# Power_MPU.net
KiCad netlist of a schematic drawn in Altium Designer
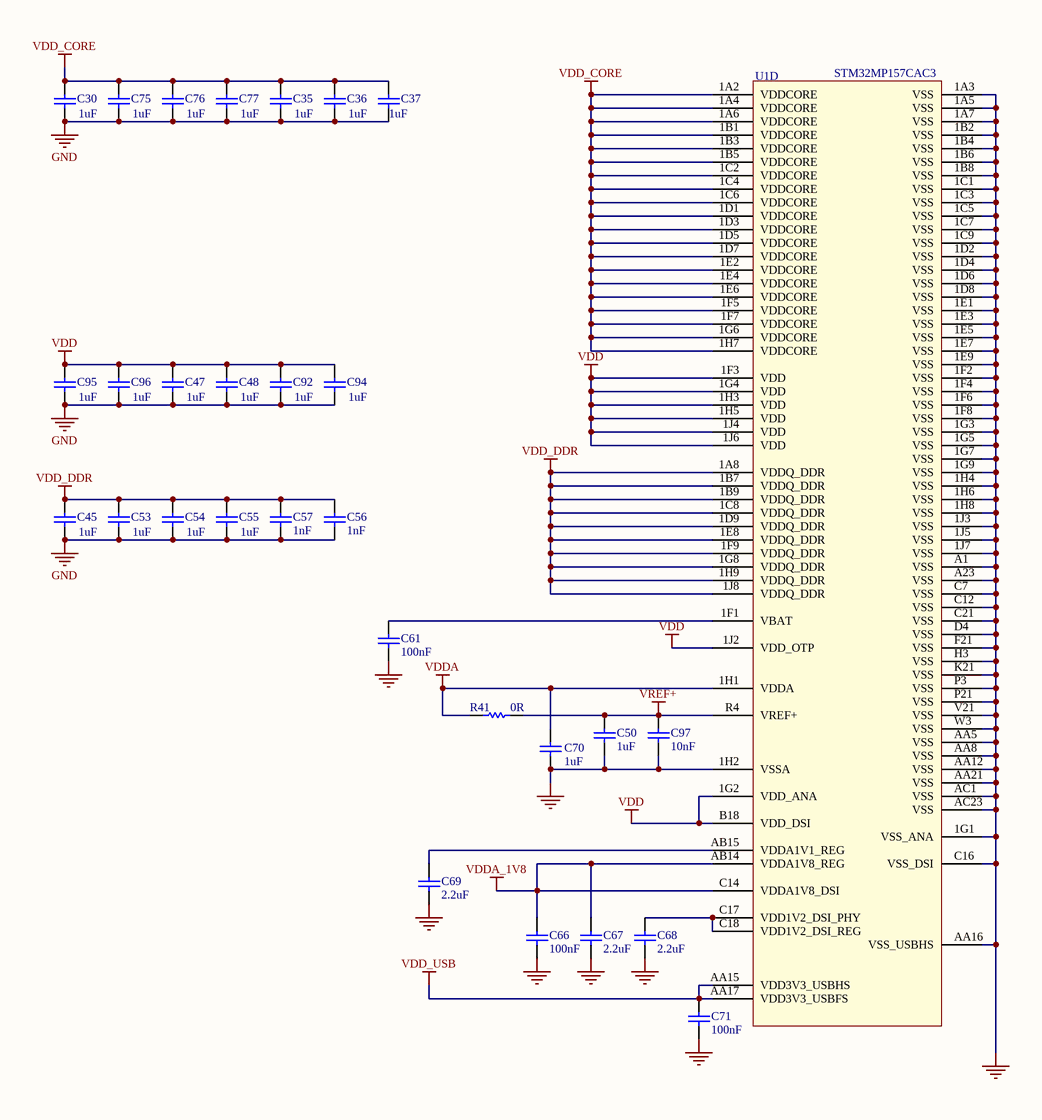
[diagram p0: Power_MPU.SchDoc]

(export (version "E")
  (design (tool "Eeschema 10.0.6"))
  (components
    (comp (ref "C30")
      (value "1uF")
      (footprint "C0402")
      (description "Capacitor,1uF,6V3,X5R,10%,0402")
      (fields
        (field (name "INTERNAL_PART_NUMBER") "MCD-00095")
        (field (name "MANUFACTURER_PART_NUMBER") "GRM155R60J105KE19")
        (field (name "PROVIDED_BY") "Subcon")
      )
      (libsource (lib "MCD_PARTS_database") (part "Capacitor"))
    )
    (comp (ref "C35")
      (value "1uF")
      (footprint "C0402")
      (description "Capacitor,1uF,6V3,X5R,10%,0402")
      (fields
        (field (name "INTERNAL_PART_NUMBER") "MCD-00095")
        (field (name "MANUFACTURER_PART_NUMBER") "GRM155R60J105KE19")
        (field (name "PROVIDED_BY") "Subcon")
      )
      (libsource (lib "MCD_PARTS_database") (part "Capacitor"))
    )
    (comp (ref "C36")
      (value "1uF")
      (footprint "C0402")
      (description "Capacitor,1uF,6V3,X5R,10%,0402")
      (fields
        (field (name "INTERNAL_PART_NUMBER") "MCD-00095")
        (field (name "MANUFACTURER_PART_NUMBER") "GRM155R60J105KE19")
        (field (name "PROVIDED_BY") "Subcon")
      )
      (libsource (lib "MCD_PARTS_database") (part "Capacitor"))
    )
    (comp (ref "C37")
      (value "1uF")
      (footprint "C0402")
      (description "Capacitor,1uF,6V3,X5R,10%,0402")
      (fields
        (field (name "INTERNAL_PART_NUMBER") "MCD-00095")
        (field (name "MANUFACTURER_PART_NUMBER") "GRM155R60J105KE19")
        (field (name "PROVIDED_BY") "Subcon")
      )
      (libsource (lib "MCD_PARTS_database") (part "Capacitor"))
    )
    (comp (ref "C45")
      (value "1uF")
      (footprint "C0402")
      (description "Capacitor,1uF,6V3,X5R,10%,0402")
      (fields
        (field (name "INTERNAL_PART_NUMBER") "MCD-00095")
        (field (name "MANUFACTURER_PART_NUMBER") "GRM155R60J105KE19")
        (field (name "PROVIDED_BY") "Subcon")
      )
      (libsource (lib "MCD_PARTS_database") (part "Capacitor"))
    )
    (comp (ref "C47")
      (value "1uF")
      (footprint "C0402")
      (description "Capacitor,1uF,6V3,X5R,10%,0402")
      (fields
        (field (name "INTERNAL_PART_NUMBER") "MCD-00095")
        (field (name "MANUFACTURER_PART_NUMBER") "GRM155R60J105KE19")
        (field (name "PROVIDED_BY") "Subcon")
      )
      (libsource (lib "MCD_PARTS_database") (part "Capacitor"))
    )
    (comp (ref "C48")
      (value "1uF")
      (footprint "C0402")
      (description "Capacitor,1uF,6V3,X5R,10%,0402")
      (fields
        (field (name "INTERNAL_PART_NUMBER") "MCD-00095")
        (field (name "MANUFACTURER_PART_NUMBER") "GRM155R60J105KE19")
        (field (name "PROVIDED_BY") "Subcon")
      )
      (libsource (lib "MCD_PARTS_database") (part "Capacitor"))
    )
    (comp (ref "C50")
      (value "1uF")
      (footprint "C0402")
      (description "Capacitor,1uF,6V3,X5R,10%,0402")
      (fields
        (field (name "INTERNAL_PART_NUMBER") "MCD-00095")
        (field (name "MANUFACTURER_PART_NUMBER") "GRM155R60J105KE19")
        (field (name "PROVIDED_BY") "Subcon")
      )
      (libsource (lib "MCD_PARTS_database") (part "Capacitor"))
    )
    (comp (ref "C53")
      (value "1uF")
      (footprint "C0402")
      (description "Capacitor,1uF,6V3,X5R,10%,0402")
      (fields
        (field (name "INTERNAL_PART_NUMBER") "MCD-00095")
        (field (name "MANUFACTURER_PART_NUMBER") "GRM155R60J105KE19")
        (field (name "PROVIDED_BY") "Subcon")
      )
      (libsource (lib "MCD_PARTS_database") (part "Capacitor"))
    )
    (comp (ref "C54")
      (value "1uF")
      (footprint "C0402")
      (description "Capacitor,1uF,6V3,X5R,10%,0402")
      (fields
        (field (name "INTERNAL_PART_NUMBER") "MCD-00095")
        (field (name "MANUFACTURER_PART_NUMBER") "GRM155R60J105KE19")
        (field (name "PROVIDED_BY") "Subcon")
      )
      (libsource (lib "MCD_PARTS_database") (part "Capacitor"))
    )
    (comp (ref "C55")
      (value "1uF")
      (footprint "C0402")
      (description "Capacitor,1uF,6V3,X5R,10%,0402")
      (fields
        (field (name "INTERNAL_PART_NUMBER") "MCD-00095")
        (field (name "MANUFACTURER_PART_NUMBER") "GRM155R60J105KE19")
        (field (name "PROVIDED_BY") "Subcon")
      )
      (libsource (lib "MCD_PARTS_database") (part "Capacitor"))
    )
    (comp (ref "C56")
      (value "1nF")
      (footprint "C0402")
      (description "Capacitor,1nF,16V,X7R,10%,0402")
      (fields
        (field (name "INTERNAL_PART_NUMBER") "MCD-00198")
        (field (name "MANUFACTURER_PART_NUMBER") "CC0402KRX7R7BB102")
        (field (name "PROVIDED_BY") "Subcon")
      )
      (libsource (lib "MCD_PARTS_database") (part "Capacitor"))
    )
    (comp (ref "C57")
      (value "1nF")
      (footprint "C0402")
      (description "Capacitor,1nF,16V,X7R,10%,0402")
      (fields
        (field (name "INTERNAL_PART_NUMBER") "MCD-00198")
        (field (name "MANUFACTURER_PART_NUMBER") "CC0402KRX7R7BB102")
        (field (name "PROVIDED_BY") "Subcon")
      )
      (libsource (lib "MCD_PARTS_database") (part "Capacitor"))
    )
    (comp (ref "C61")
      (value "100nF")
      (footprint "C0402")
      (description "Capacitor,100nF,16V,X7R,10%,0402")
      (fields
        (field (name "INTERNAL_PART_NUMBER") "MCD-00006")
        (field (name "MANUFACTURER_PART_NUMBER") "CC0402KRX7R7BB104")
        (field (name "PROVIDED_BY") "Subcon")
      )
      (libsource (lib "MCD_PARTS_database") (part "Capacitor"))
    )
    (comp (ref "C66")
      (value "100nF")
      (footprint "C0402")
      (description "Capacitor, MLCC, 100nF, 16V, X7R, 10%, 0402, T=0.5mm")
      (fields
        (field (name "INTERNAL_PART_NUMBER") "MCD-00006")
        (field (name "MANUFACTURER_PART_NUMBER") "CC0402KRX7R7BB104")
        (field (name "PROVIDED_BY") "SUBCO")
      )
      (libsource (lib "MCD_PARTS_database") (part "Capacitor"))
    )
    (comp (ref "C67")
      (value "2.2uF")
      (footprint "C0402")
      (description "Capacitor,MLCC,2.2uF,6V3,X5R,10%,0402,T=0.5")
      (fields
        (field (name "INTERNAL_PART_NUMBER") "MCD-01823")
        (field (name "MANUFACTURER_PART_NUMBER") "GRM155R60J225KE95D")
        (field (name "PROVIDED_BY") "SUBCO")
      )
      (libsource (lib "MCD_PARTS_database") (part "Capacitor"))
    )
    (comp (ref "C68")
      (value "2.2uF")
      (footprint "C0402")
      (description "Capacitor,MLCC,2.2uF,6V3,X5R,10%,0402,T=0.5")
      (fields
        (field (name "INTERNAL_PART_NUMBER") "MCD-01823")
        (field (name "MANUFACTURER_PART_NUMBER") "GRM155R60J225KE95D")
        (field (name "PROVIDED_BY") "SUBCO")
      )
      (libsource (lib "MCD_PARTS_database") (part "Capacitor"))
    )
    (comp (ref "C69")
      (value "2.2uF")
      (footprint "C0402")
      (description "Capacitor,MLCC,2.2uF,6V3,X5R,10%,0402,T=0.5")
      (fields
        (field (name "INTERNAL_PART_NUMBER") "MCD-01823")
        (field (name "MANUFACTURER_PART_NUMBER") "GRM155R60J225KE95D")
        (field (name "PROVIDED_BY") "SUBCO")
      )
      (libsource (lib "MCD_PARTS_database") (part "Capacitor"))
    )
    (comp (ref "C70")
      (value "1uF")
      (footprint "C0402")
      (description "Capacitor,1uF,6V3,X5R,10%,0402")
      (fields
        (field (name "INTERNAL_PART_NUMBER") "MCD-00095")
        (field (name "MANUFACTURER_PART_NUMBER") "GRM155R60J105KE19")
        (field (name "PROVIDED_BY") "Subcon")
      )
      (libsource (lib "MCD_PARTS_database") (part "Capacitor"))
    )
    (comp (ref "C71")
      (value "100nF")
      (footprint "C0402")
      (description "Capacitor,100nF,16V,X7R,10%,0402")
      (fields
        (field (name "INTERNAL_PART_NUMBER") "MCD-00006")
        (field (name "MANUFACTURER_PART_NUMBER") "CC0402KRX7R7BB104")
        (field (name "PROVIDED_BY") "Subcon")
      )
      (libsource (lib "MCD_PARTS_database") (part "Capacitor"))
    )
    (comp (ref "C75")
      (value "1uF")
      (footprint "C0402")
      (description "Capacitor,1uF,6V3,X5R,10%,0402")
      (fields
        (field (name "INTERNAL_PART_NUMBER") "MCD-00095")
        (field (name "MANUFACTURER_PART_NUMBER") "GRM155R60J105KE19")
        (field (name "PROVIDED_BY") "Subcon")
      )
      (libsource (lib "MCD_PARTS_database") (part "Capacitor"))
    )
    (comp (ref "C76")
      (value "1uF")
      (footprint "C0402")
      (description "Capacitor,1uF,6V3,X5R,10%,0402")
      (fields
        (field (name "INTERNAL_PART_NUMBER") "MCD-00095")
        (field (name "MANUFACTURER_PART_NUMBER") "GRM155R60J105KE19")
        (field (name "PROVIDED_BY") "Subcon")
      )
      (libsource (lib "MCD_PARTS_database") (part "Capacitor"))
    )
    (comp (ref "C77")
      (value "1uF")
      (footprint "C0402")
      (description "Capacitor,1uF,6V3,X5R,10%,0402")
      (fields
        (field (name "INTERNAL_PART_NUMBER") "MCD-00095")
        (field (name "MANUFACTURER_PART_NUMBER") "GRM155R60J105KE19")
        (field (name "PROVIDED_BY") "Subcon")
      )
      (libsource (lib "MCD_PARTS_database") (part "Capacitor"))
    )
    (comp (ref "C92")
      (value "1uF")
      (footprint "C0402")
      (description "Capacitor,1uF,6V3,X5R,10%,0402")
      (fields
        (field (name "INTERNAL_PART_NUMBER") "MCD-00095")
        (field (name "MANUFACTURER_PART_NUMBER") "GRM155R60J105KE19")
        (field (name "PROVIDED_BY") "Subcon")
      )
      (libsource (lib "MCD_PARTS_database") (part "Capacitor"))
    )
    (comp (ref "C94")
      (value "1uF")
      (footprint "C0402")
      (description "Capacitor,1uF,6V3,X5R,10%,0402")
      (fields
        (field (name "INTERNAL_PART_NUMBER") "MCD-00095")
        (field (name "MANUFACTURER_PART_NUMBER") "GRM155R60J105KE19")
        (field (name "PROVIDED_BY") "Subcon")
      )
      (libsource (lib "MCD_PARTS_database") (part "Capacitor"))
    )
    (comp (ref "C95")
      (value "1uF")
      (footprint "C0402")
      (description "Capacitor,1uF,6V3,X5R,10%,0402")
      (fields
        (field (name "INTERNAL_PART_NUMBER") "MCD-00095")
        (field (name "MANUFACTURER_PART_NUMBER") "GRM155R60J105KE19")
        (field (name "PROVIDED_BY") "Subcon")
      )
      (libsource (lib "MCD_PARTS_database") (part "Capacitor"))
    )
    (comp (ref "C96")
      (value "1uF")
      (footprint "C0402")
      (description "Capacitor,1uF,6V3,X5R,10%,0402")
      (fields
        (field (name "INTERNAL_PART_NUMBER") "MCD-00095")
        (field (name "MANUFACTURER_PART_NUMBER") "GRM155R60J105KE19")
        (field (name "PROVIDED_BY") "Subcon")
      )
      (libsource (lib "MCD_PARTS_database") (part "Capacitor"))
    )
    (comp (ref "C97")
      (value "10nF")
      (footprint "C0402")
      (description "Capacitor, MLCC, 10nF, 16V, X7R, 10%, 0402, T=0.5mm")
      (fields
        (field (name "INTERNAL_PART_NUMBER") "MCD-00011")
        (field (name "MANUFACTURER_PART_NUMBER") "CC0402KRX7R7BB103")
        (field (name "PROVIDED_BY") "SUBCO")
      )
      (libsource (lib "MCD_PARTS_database") (part "Capacitor"))
    )
    (comp (ref "R41")
      (value "0R")
      (footprint "R0402")
      (description "Resistor,0R,0402,5%,1/16W")
      (fields
        (field (name "INTERNAL_PART_NUMBER") "MCD-00052")
        (field (name "MANUFACTURER_PART_NUMBER") "RC0402JR-070RL")
        (field (name "PROVIDED_BY") "Subcon")
      )
      (libsource (lib "MCD_PARTS_database") (part "Resistor"))
    )
    (comp (ref "U1")
      (value "STM32MP157CAC3")
      (footprint "ICC_TFBGA361_12X12_STM32MP157CAC3_P050-065")
      (description "MPU TFBGA12x12 secure boot+crypto")
      (fields
        (field (name "INTERNAL_PART_NUMBER") "MCD-00677")
        (field (name "MANUFACTURER") "STMICROELECTRONICS")
        (field (name "PROVIDED_BY") "STM")
      )
      (libsource (lib "MCD_PARTS_database") (part "STM32MP157CAC3"))
    )
  )
  (nets
    (net (code "1") (name "GND") (class "Default")
      (node (ref "C30") (pin "1") (pinfunction "1_1") (pintype "passive"))
      (node (ref "C35") (pin "1") (pinfunction "1_1") (pintype "passive"))
      (node (ref "C36") (pin "1") (pinfunction "1_1") (pintype "passive"))
      (node (ref "C37") (pin "1") (pinfunction "1_1") (pintype "passive"))
      (node (ref "C45") (pin "1") (pinfunction "1_1") (pintype "passive"))
      (node (ref "C47") (pin "1") (pinfunction "1_1") (pintype "passive"))
      (node (ref "C48") (pin "1") (pinfunction "1_1") (pintype "passive"))
      (node (ref "C50") (pin "1") (pinfunction "1_1") (pintype "passive"))
      (node (ref "C53") (pin "1") (pinfunction "1_1") (pintype "passive"))
      (node (ref "C54") (pin "1") (pinfunction "1_1") (pintype "passive"))
      (node (ref "C55") (pin "1") (pinfunction "1_1") (pintype "passive"))
      (node (ref "C56") (pin "1") (pinfunction "1_1") (pintype "passive"))
      (node (ref "C57") (pin "1") (pinfunction "1_1") (pintype "passive"))
      (node (ref "C61") (pin "1") (pinfunction "1_1") (pintype "passive"))
      (node (ref "C66") (pin "1") (pinfunction "1_1") (pintype "passive"))
      (node (ref "C67") (pin "1") (pinfunction "1_1") (pintype "passive"))
      (node (ref "C68") (pin "1") (pinfunction "1_1") (pintype "passive"))
      (node (ref "C69") (pin "1") (pinfunction "1_1") (pintype "passive"))
      (node (ref "C70") (pin "1") (pinfunction "1_1") (pintype "passive"))
      (node (ref "C71") (pin "1") (pinfunction "1_1") (pintype "passive"))
      (node (ref "C75") (pin "1") (pinfunction "1_1") (pintype "passive"))
      (node (ref "C76") (pin "1") (pinfunction "1_1") (pintype "passive"))
      (node (ref "C77") (pin "1") (pinfunction "1_1") (pintype "passive"))
      (node (ref "C92") (pin "1") (pinfunction "1_1") (pintype "passive"))
      (node (ref "C94") (pin "1") (pinfunction "1_1") (pintype "passive"))
      (node (ref "C95") (pin "1") (pinfunction "1_1") (pintype "passive"))
      (node (ref "C96") (pin "1") (pinfunction "1_1") (pintype "passive"))
      (node (ref "C97") (pin "1") (pinfunction "1_1") (pintype "passive"))
      (node (ref "U1") (pin "1A3") (pinfunction "VSS_1A3") (pintype "passive"))
      (node (ref "U1") (pin "1A5") (pinfunction "VSS_1A5") (pintype "passive"))
      (node (ref "U1") (pin "1A7") (pinfunction "VSS_1A7") (pintype "passive"))
      (node (ref "U1") (pin "1B2") (pinfunction "VSS_1B2") (pintype "passive"))
      (node (ref "U1") (pin "1B4") (pinfunction "VSS_1B4") (pintype "passive"))
      (node (ref "U1") (pin "1B6") (pinfunction "VSS_1B6") (pintype "passive"))
      (node (ref "U1") (pin "1B8") (pinfunction "VSS_1B8") (pintype "passive"))
      (node (ref "U1") (pin "1C1") (pinfunction "VSS_1C1") (pintype "passive"))
      (node (ref "U1") (pin "1C3") (pinfunction "VSS_1C3") (pintype "passive"))
      (node (ref "U1") (pin "1C5") (pinfunction "VSS_1C5") (pintype "passive"))
      (node (ref "U1") (pin "1C7") (pinfunction "VSS_1C7") (pintype "passive"))
      (node (ref "U1") (pin "1C9") (pinfunction "VSS_1C9") (pintype "passive"))
      (node (ref "U1") (pin "1D2") (pinfunction "VSS_1D2") (pintype "passive"))
      (node (ref "U1") (pin "1D4") (pinfunction "VSS_1D4") (pintype "passive"))
      (node (ref "U1") (pin "1D6") (pinfunction "VSS_1D6") (pintype "passive"))
      (node (ref "U1") (pin "1D8") (pinfunction "VSS_1D8") (pintype "passive"))
      (node (ref "U1") (pin "1E1") (pinfunction "VSS_1E1") (pintype "passive"))
      (node (ref "U1") (pin "1E3") (pinfunction "VSS_1E3") (pintype "passive"))
      (node (ref "U1") (pin "1E5") (pinfunction "VSS_1E5") (pintype "passive"))
      (node (ref "U1") (pin "1E7") (pinfunction "VSS_1E7") (pintype "passive"))
      (node (ref "U1") (pin "1E9") (pinfunction "VSS_1E9") (pintype "passive"))
      (node (ref "U1") (pin "1F2") (pinfunction "VSS_1F2") (pintype "passive"))
      (node (ref "U1") (pin "1F4") (pinfunction "VSS_1F4") (pintype "passive"))
      (node (ref "U1") (pin "1F6") (pinfunction "VSS_1F6") (pintype "passive"))
      (node (ref "U1") (pin "1F8") (pinfunction "VSS_1F8") (pintype "passive"))
      (node (ref "U1") (pin "1G1") (pinfunction "VSS_ANA_1G1") (pintype "passive"))
      (node (ref "U1") (pin "1G3") (pinfunction "VSS_1G3") (pintype "passive"))
      (node (ref "U1") (pin "1G5") (pinfunction "VSS_1G5") (pintype "passive"))
      (node (ref "U1") (pin "1G7") (pinfunction "VSS_1G7") (pintype "passive"))
      (node (ref "U1") (pin "1G9") (pinfunction "VSS_1G9") (pintype "passive"))
      (node (ref "U1") (pin "1H2") (pinfunction "VSSA_1H2") (pintype "passive"))
      (node (ref "U1") (pin "1H4") (pinfunction "VSS_1H4") (pintype "passive"))
      (node (ref "U1") (pin "1H6") (pinfunction "VSS_1H6") (pintype "passive"))
      (node (ref "U1") (pin "1H8") (pinfunction "VSS_1H8") (pintype "passive"))
      (node (ref "U1") (pin "1J3") (pinfunction "VSS_1J3") (pintype "passive"))
      (node (ref "U1") (pin "1J5") (pinfunction "VSS_1J5") (pintype "passive"))
      (node (ref "U1") (pin "1J7") (pinfunction "VSS_1J7") (pintype "passive"))
      (node (ref "U1") (pin "A1") (pinfunction "VSS_A1") (pintype "passive"))
      (node (ref "U1") (pin "A23") (pinfunction "VSS_A23") (pintype "passive"))
      (node (ref "U1") (pin "AA12") (pinfunction "VSS_AA12") (pintype "passive"))
      (node (ref "U1") (pin "AA16") (pinfunction "VSS_USBHS_AA16") (pintype "passive"))
      (node (ref "U1") (pin "AA21") (pinfunction "VSS_AA21") (pintype "passive"))
      (node (ref "U1") (pin "AA5") (pinfunction "VSS_AA5") (pintype "passive"))
      (node (ref "U1") (pin "AA8") (pinfunction "VSS_AA8") (pintype "passive"))
      (node (ref "U1") (pin "AC1") (pinfunction "VSS_AC1") (pintype "passive"))
      (node (ref "U1") (pin "AC23") (pinfunction "VSS_AC23") (pintype "passive"))
      (node (ref "U1") (pin "C12") (pinfunction "VSS_C12") (pintype "passive"))
      (node (ref "U1") (pin "C16") (pinfunction "VSS_DSI_C16") (pintype "passive"))
      (node (ref "U1") (pin "C21") (pinfunction "VSS_C21") (pintype "passive"))
      (node (ref "U1") (pin "C7") (pinfunction "VSS_C7") (pintype "passive"))
      (node (ref "U1") (pin "D4") (pinfunction "VSS_D4") (pintype "passive"))
      (node (ref "U1") (pin "F21") (pinfunction "VSS_F21") (pintype "passive"))
      (node (ref "U1") (pin "H3") (pinfunction "VSS_H3") (pintype "passive"))
      (node (ref "U1") (pin "K21") (pinfunction "VSS_K21") (pintype "passive"))
      (node (ref "U1") (pin "P21") (pinfunction "VSS_P21") (pintype "passive"))
      (node (ref "U1") (pin "P3") (pinfunction "VSS_P3") (pintype "passive"))
      (node (ref "U1") (pin "V21") (pinfunction "VSS_V21") (pintype "passive"))
      (node (ref "U1") (pin "W3") (pinfunction "VSS_W3") (pintype "passive"))
    )
    (net (code "2") (name "Net-(U1D-VBAT)") (class "Default")
      (node (ref "C61") (pin "2") (pinfunction "2_2") (pintype "passive"))
      (node (ref "U1") (pin "1F1") (pinfunction "VBAT_1F1") (pintype "passive"))
    )
    (net (code "3") (name "Net-(U1D-VDD1V2_DSI_PHY)") (class "Default")
      (node (ref "C68") (pin "2") (pinfunction "2_2") (pintype "passive"))
      (node (ref "U1") (pin "C17") (pinfunction "VDD1V2_DSI_PHY_C17") (pintype "passive"))
      (node (ref "U1") (pin "C18") (pinfunction "VDD1V2_DSI_REG_C18") (pintype "passive"))
    )
    (net (code "4") (name "Net-(U1D-VDDA1V1_REG)") (class "Default")
      (node (ref "C69") (pin "2") (pinfunction "2_2") (pintype "passive"))
      (node (ref "U1") (pin "AB15") (pinfunction "VDDA1V1_REG_AB15") (pintype "passive"))
    )
    (net (code "5") (name "VDD") (class "Default")
      (node (ref "C47") (pin "2") (pinfunction "2_2") (pintype "passive"))
      (node (ref "C48") (pin "2") (pinfunction "2_2") (pintype "passive"))
      (node (ref "C92") (pin "2") (pinfunction "2_2") (pintype "passive"))
      (node (ref "C94") (pin "2") (pinfunction "2_2") (pintype "passive"))
      (node (ref "C95") (pin "2") (pinfunction "2_2") (pintype "passive"))
      (node (ref "C96") (pin "2") (pinfunction "2_2") (pintype "passive"))
      (node (ref "U1") (pin "1F3") (pinfunction "VDD_1F3") (pintype "passive"))
      (node (ref "U1") (pin "1G2") (pinfunction "VDD_ANA_1G2") (pintype "passive"))
      (node (ref "U1") (pin "1G4") (pinfunction "VDD_1G4") (pintype "passive"))
      (node (ref "U1") (pin "1H3") (pinfunction "VDD_1H3") (pintype "passive"))
      (node (ref "U1") (pin "1H5") (pinfunction "VDD_1H5") (pintype "passive"))
      (node (ref "U1") (pin "1J2") (pinfunction "VDD_OTP_1J2") (pintype "passive"))
      (node (ref "U1") (pin "1J4") (pinfunction "VDD_1J4") (pintype "passive"))
      (node (ref "U1") (pin "1J6") (pinfunction "VDD_1J6") (pintype "passive"))
      (node (ref "U1") (pin "B18") (pinfunction "VDD_DSI_B18") (pintype "passive"))
    )
    (net (code "6") (name "VDDA") (class "Default")
      (node (ref "C70") (pin "2") (pinfunction "2_2") (pintype "passive"))
      (node (ref "R41") (pin "1") (pinfunction "1_1") (pintype "passive"))
      (node (ref "U1") (pin "1H1") (pinfunction "VDDA_1H1") (pintype "passive"))
    )
    (net (code "7") (name "VDDA_1V8") (class "Default")
      (node (ref "C66") (pin "2") (pinfunction "2_2") (pintype "passive"))
      (node (ref "C67") (pin "2") (pinfunction "2_2") (pintype "passive"))
      (node (ref "U1") (pin "AB14") (pinfunction "VDDA1V8_REG_AB14") (pintype "passive"))
      (node (ref "U1") (pin "C14") (pinfunction "VDDA1V8_DSI_C14") (pintype "passive"))
    )
    (net (code "8") (name "VDD_CORE") (class "Default")
      (node (ref "C30") (pin "2") (pinfunction "2_2") (pintype "passive"))
      (node (ref "C35") (pin "2") (pinfunction "2_2") (pintype "passive"))
      (node (ref "C36") (pin "2") (pinfunction "2_2") (pintype "passive"))
      (node (ref "C37") (pin "2") (pinfunction "2_2") (pintype "passive"))
      (node (ref "C75") (pin "2") (pinfunction "2_2") (pintype "passive"))
      (node (ref "C76") (pin "2") (pinfunction "2_2") (pintype "passive"))
      (node (ref "C77") (pin "2") (pinfunction "2_2") (pintype "passive"))
      (node (ref "U1") (pin "1A2") (pinfunction "VDDCORE_1A2") (pintype "passive"))
      (node (ref "U1") (pin "1A4") (pinfunction "VDDCORE_1A4") (pintype "passive"))
      (node (ref "U1") (pin "1A6") (pinfunction "VDDCORE_1A6") (pintype "passive"))
      (node (ref "U1") (pin "1B1") (pinfunction "VDDCORE_1B1") (pintype "passive"))
      (node (ref "U1") (pin "1B3") (pinfunction "VDDCORE_1B3") (pintype "passive"))
      (node (ref "U1") (pin "1B5") (pinfunction "VDDCORE_1B5") (pintype "passive"))
      (node (ref "U1") (pin "1C2") (pinfunction "VDDCORE_1C2") (pintype "passive"))
      (node (ref "U1") (pin "1C4") (pinfunction "VDDCORE_1C4") (pintype "passive"))
      (node (ref "U1") (pin "1C6") (pinfunction "VDDCORE_1C6") (pintype "passive"))
      (node (ref "U1") (pin "1D1") (pinfunction "VDDCORE_1D1") (pintype "passive"))
      (node (ref "U1") (pin "1D3") (pinfunction "VDDCORE_1D3") (pintype "passive"))
      (node (ref "U1") (pin "1D5") (pinfunction "VDDCORE_1D5") (pintype "passive"))
      (node (ref "U1") (pin "1D7") (pinfunction "VDDCORE_1D7") (pintype "passive"))
      (node (ref "U1") (pin "1E2") (pinfunction "VDDCORE_1E2") (pintype "passive"))
      (node (ref "U1") (pin "1E4") (pinfunction "VDDCORE_1E4") (pintype "passive"))
      (node (ref "U1") (pin "1E6") (pinfunction "VDDCORE_1E6") (pintype "passive"))
      (node (ref "U1") (pin "1F5") (pinfunction "VDDCORE_1F5") (pintype "passive"))
      (node (ref "U1") (pin "1F7") (pinfunction "VDDCORE_1F7") (pintype "passive"))
      (node (ref "U1") (pin "1G6") (pinfunction "VDDCORE_1G6") (pintype "passive"))
      (node (ref "U1") (pin "1H7") (pinfunction "VDDCORE_1H7") (pintype "passive"))
    )
    (net (code "9") (name "VDD_DDR") (class "Default")
      (node (ref "C45") (pin "2") (pinfunction "2_2") (pintype "passive"))
      (node (ref "C53") (pin "2") (pinfunction "2_2") (pintype "passive"))
      (node (ref "C54") (pin "2") (pinfunction "2_2") (pintype "passive"))
      (node (ref "C55") (pin "2") (pinfunction "2_2") (pintype "passive"))
      (node (ref "C56") (pin "2") (pinfunction "2_2") (pintype "passive"))
      (node (ref "C57") (pin "2") (pinfunction "2_2") (pintype "passive"))
      (node (ref "U1") (pin "1A8") (pinfunction "VDDQ_DDR_1A8") (pintype "passive"))
      (node (ref "U1") (pin "1B7") (pinfunction "VDDQ_DDR_1B7") (pintype "passive"))
      (node (ref "U1") (pin "1B9") (pinfunction "VDDQ_DDR_1B9") (pintype "passive"))
      (node (ref "U1") (pin "1C8") (pinfunction "VDDQ_DDR_1C8") (pintype "passive"))
      (node (ref "U1") (pin "1D9") (pinfunction "VDDQ_DDR_1D9") (pintype "passive"))
      (node (ref "U1") (pin "1E8") (pinfunction "VDDQ_DDR_1E8") (pintype "passive"))
      (node (ref "U1") (pin "1F9") (pinfunction "VDDQ_DDR_1F9") (pintype "passive"))
      (node (ref "U1") (pin "1G8") (pinfunction "VDDQ_DDR_1G8") (pintype "passive"))
      (node (ref "U1") (pin "1H9") (pinfunction "VDDQ_DDR_1H9") (pintype "passive"))
      (node (ref "U1") (pin "1J8") (pinfunction "VDDQ_DDR_1J8") (pintype "passive"))
    )
    (net (code "10") (name "VDD_USB") (class "Default")
      (node (ref "C71") (pin "2") (pinfunction "2_2") (pintype "passive"))
      (node (ref "U1") (pin "AA15") (pinfunction "VDD3V3_USBHS_AA15") (pintype "passive"))
      (node (ref "U1") (pin "AA17") (pinfunction "VDD3V3_USBFS_AA17") (pintype "passive"))
    )
    (net (code "11") (name "VREF+") (class "Default")
      (node (ref "C50") (pin "2") (pinfunction "2_2") (pintype "passive"))
      (node (ref "C97") (pin "2") (pinfunction "2_2") (pintype "passive"))
      (node (ref "R41") (pin "2") (pinfunction "2_2") (pintype "passive"))
      (node (ref "U1") (pin "R4") (pinfunction "VREF+_R4") (pintype "passive"))
    )
  )
)
